# main.net
KiCad netlist of a schematic drawn in Altium Designer
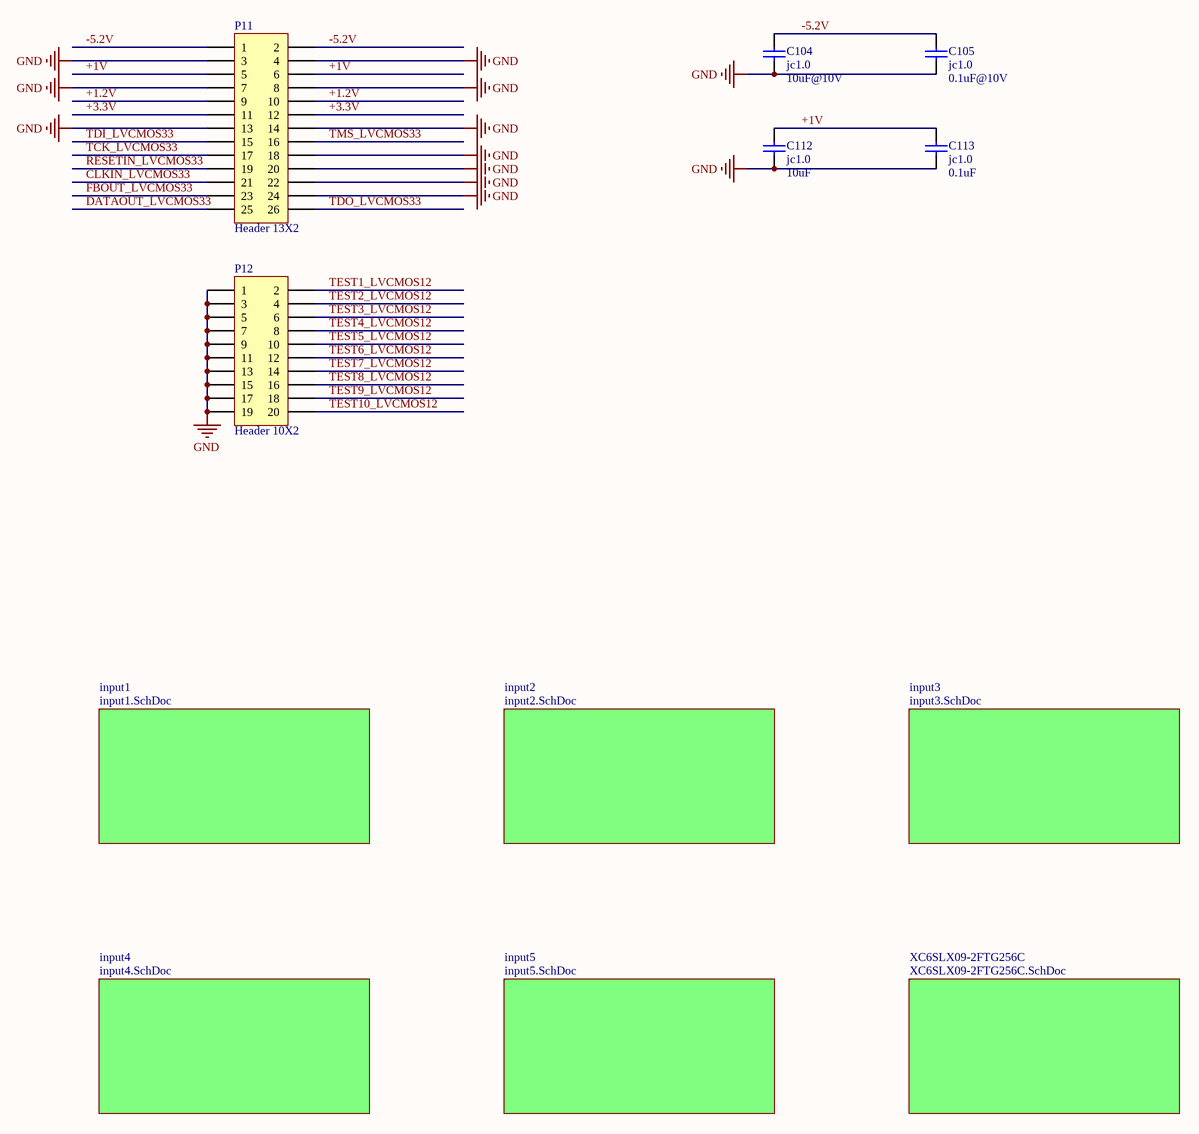
[diagram p0: main.SchDoc]

(export (version "E")
  (design (tool "Eeschema 10.0.6"))
  (components
    (comp (ref "C104")
      (value "jc1.0")
      (footprint "0805")
      (description "Capacitor")
      (fields (field (name "ALTIUM_VALUE") "10uF@10V") (field (name "PUBLISHER") "Altium Limited"))
      (libsource (lib "LIB01DXP2006SchLib") (part "Cap"))
    )
    (comp (ref "C105")
      (value "jc1.0")
      (footprint "0805")
      (description "Capacitor")
      (fields (field (name "ALTIUM_VALUE") "0.1uF@10V") (field (name "PUBLISHER") "Altium Limited"))
      (libsource (lib "LIB01DXP2006SchLib") (part "Cap"))
    )
    (comp (ref "C112")
      (value "jc1.0")
      (footprint "0805")
      (description "Capacitor")
      (fields (field (name "ALTIUM_VALUE") "10uF") (field (name "PUBLISHER") "Altium Limited"))
      (libsource (lib "LIB01DXP2006SchLib") (part "Cap"))
    )
    (comp (ref "C113")
      (value "jc1.0")
      (footprint "0805")
      (description "Capacitor")
      (fields (field (name "ALTIUM_VALUE") "0.1uF") (field (name "PUBLISHER") "Altium Limited"))
      (libsource (lib "LIB01DXP2006SchLib") (part "Cap"))
    )
    (comp (ref "P11")
      (value "Header 13X2")
      (footprint "HDR2X13")
      (description "Header, 13-Pin, Dual row")
      (fields (field (name "PUBLISHER") "Altium Limited"))
      (libsource (lib "Miscellaneous Connectors") (part "Header 13X2"))
    )
    (comp (ref "P12")
      (value "Header 10X2")
      (footprint "HDR2X10")
      (description "Header, 10-Pin, Dual row")
      (fields (field (name "PUBLISHER") "Altium Limited"))
      (libsource (lib "Miscellaneous Connectors") (part "Header 10X2"))
    )
  )
  (nets
    (net (code "1") (name "/+1.2V") (class "Default")
      (node (ref "P11") (pin "10") (pinfunction "10_10") (pintype "passive"))
      (node (ref "P11") (pin "9") (pinfunction "9_9") (pintype "passive"))
    )
    (net (code "2") (name "/+1V") (class "Default")
      (node (ref "C112") (pin "2") (pinfunction "2_2") (pintype "passive"))
      (node (ref "C113") (pin "2") (pinfunction "2_2") (pintype "passive"))
      (node (ref "P11") (pin "5") (pinfunction "5_5") (pintype "passive"))
      (node (ref "P11") (pin "6") (pinfunction "6_6") (pintype "passive"))
    )
    (net (code "3") (name "/+3.3V") (class "Default")
      (node (ref "P11") (pin "11") (pinfunction "11_11") (pintype "passive"))
      (node (ref "P11") (pin "12") (pinfunction "12_12") (pintype "passive"))
    )
    (net (code "4") (name "/-5.2V") (class "Default")
      (node (ref "C104") (pin "2") (pinfunction "2_2") (pintype "passive"))
      (node (ref "C105") (pin "2") (pinfunction "2_2") (pintype "passive"))
      (node (ref "P11") (pin "1") (pinfunction "1_1") (pintype "passive"))
      (node (ref "P11") (pin "2") (pinfunction "2_2") (pintype "passive"))
    )
    (net (code "5") (name "/CLKIN_LVCMOS33") (class "Default")
      (node (ref "P11") (pin "21") (pinfunction "21_21") (pintype "passive"))
    )
    (net (code "6") (name "/DATAOUT_LVCMOS33") (class "Default")
      (node (ref "P11") (pin "25") (pinfunction "25_25") (pintype "passive"))
    )
    (net (code "7") (name "/FBOUT_LVCMOS33") (class "Default")
      (node (ref "P11") (pin "23") (pinfunction "23_23") (pintype "passive"))
    )
    (net (code "8") (name "/RESETIN_LVCMOS33") (class "Default")
      (node (ref "P11") (pin "19") (pinfunction "19_19") (pintype "passive"))
    )
    (net (code "9") (name "/TCK_LVCMOS33") (class "Default")
      (node (ref "P11") (pin "17") (pinfunction "17_17") (pintype "passive"))
    )
    (net (code "10") (name "/TDI_LVCMOS33") (class "Default")
      (node (ref "P11") (pin "15") (pinfunction "15_15") (pintype "passive"))
    )
    (net (code "11") (name "/TDO_LVCMOS33") (class "Default")
      (node (ref "P11") (pin "26") (pinfunction "26_26") (pintype "passive"))
    )
    (net (code "12") (name "/TEST1_LVCMOS12") (class "Default")
      (node (ref "P12") (pin "2") (pinfunction "2_2") (pintype "passive"))
    )
    (net (code "13") (name "/TEST2_LVCMOS12") (class "Default")
      (node (ref "P12") (pin "4") (pinfunction "4_4") (pintype "passive"))
    )
    (net (code "14") (name "/TEST3_LVCMOS12") (class "Default")
      (node (ref "P12") (pin "6") (pinfunction "6_6") (pintype "passive"))
    )
    (net (code "15") (name "/TEST4_LVCMOS12") (class "Default")
      (node (ref "P12") (pin "8") (pinfunction "8_8") (pintype "passive"))
    )
    (net (code "16") (name "/TEST5_LVCMOS12") (class "Default")
      (node (ref "P12") (pin "10") (pinfunction "10_10") (pintype "passive"))
    )
    (net (code "17") (name "/TEST6_LVCMOS12") (class "Default")
      (node (ref "P12") (pin "12") (pinfunction "12_12") (pintype "passive"))
    )
    (net (code "18") (name "/TEST7_LVCMOS12") (class "Default")
      (node (ref "P12") (pin "14") (pinfunction "14_14") (pintype "passive"))
    )
    (net (code "19") (name "/TEST8_LVCMOS12") (class "Default")
      (node (ref "P12") (pin "16") (pinfunction "16_16") (pintype "passive"))
    )
    (net (code "20") (name "/TEST9_LVCMOS12") (class "Default")
      (node (ref "P12") (pin "18") (pinfunction "18_18") (pintype "passive"))
    )
    (net (code "21") (name "/TEST10_LVCMOS12") (class "Default")
      (node (ref "P12") (pin "20") (pinfunction "20_20") (pintype "passive"))
    )
    (net (code "22") (name "/TMS_LVCMOS33") (class "Default")
      (node (ref "P11") (pin "16") (pinfunction "16_16") (pintype "passive"))
    )
    (net (code "23") (name "GND") (class "Default")
      (node (ref "C104") (pin "1") (pinfunction "1_1") (pintype "passive"))
      (node (ref "C105") (pin "1") (pinfunction "1_1") (pintype "passive"))
      (node (ref "C112") (pin "1") (pinfunction "1_1") (pintype "passive"))
      (node (ref "C113") (pin "1") (pinfunction "1_1") (pintype "passive"))
      (node (ref "P11") (pin "13") (pinfunction "13_13") (pintype "passive"))
      (node (ref "P11") (pin "14") (pinfunction "14_14") (pintype "passive"))
      (node (ref "P11") (pin "18") (pinfunction "18_18") (pintype "passive"))
      (node (ref "P11") (pin "20") (pinfunction "20_20") (pintype "passive"))
      (node (ref "P11") (pin "22") (pinfunction "22_22") (pintype "passive"))
      (node (ref "P11") (pin "24") (pinfunction "24_24") (pintype "passive"))
      (node (ref "P11") (pin "3") (pinfunction "3_3") (pintype "passive"))
      (node (ref "P11") (pin "4") (pinfunction "4_4") (pintype "passive"))
      (node (ref "P11") (pin "7") (pinfunction "7_7") (pintype "passive"))
      (node (ref "P11") (pin "8") (pinfunction "8_8") (pintype "passive"))
      (node (ref "P12") (pin "1") (pinfunction "1_1") (pintype "passive"))
      (node (ref "P12") (pin "11") (pinfunction "11_11") (pintype "passive"))
      (node (ref "P12") (pin "13") (pinfunction "13_13") (pintype "passive"))
      (node (ref "P12") (pin "15") (pinfunction "15_15") (pintype "passive"))
      (node (ref "P12") (pin "17") (pinfunction "17_17") (pintype "passive"))
      (node (ref "P12") (pin "19") (pinfunction "19_19") (pintype "passive"))
      (node (ref "P12") (pin "3") (pinfunction "3_3") (pintype "passive"))
      (node (ref "P12") (pin "5") (pinfunction "5_5") (pintype "passive"))
      (node (ref "P12") (pin "7") (pinfunction "7_7") (pintype "passive"))
      (node (ref "P12") (pin "9") (pinfunction "9_9") (pintype "passive"))
    )
  )
)
